# RGBM-04.net
KiCad netlist of a schematic drawn in Altium Designer
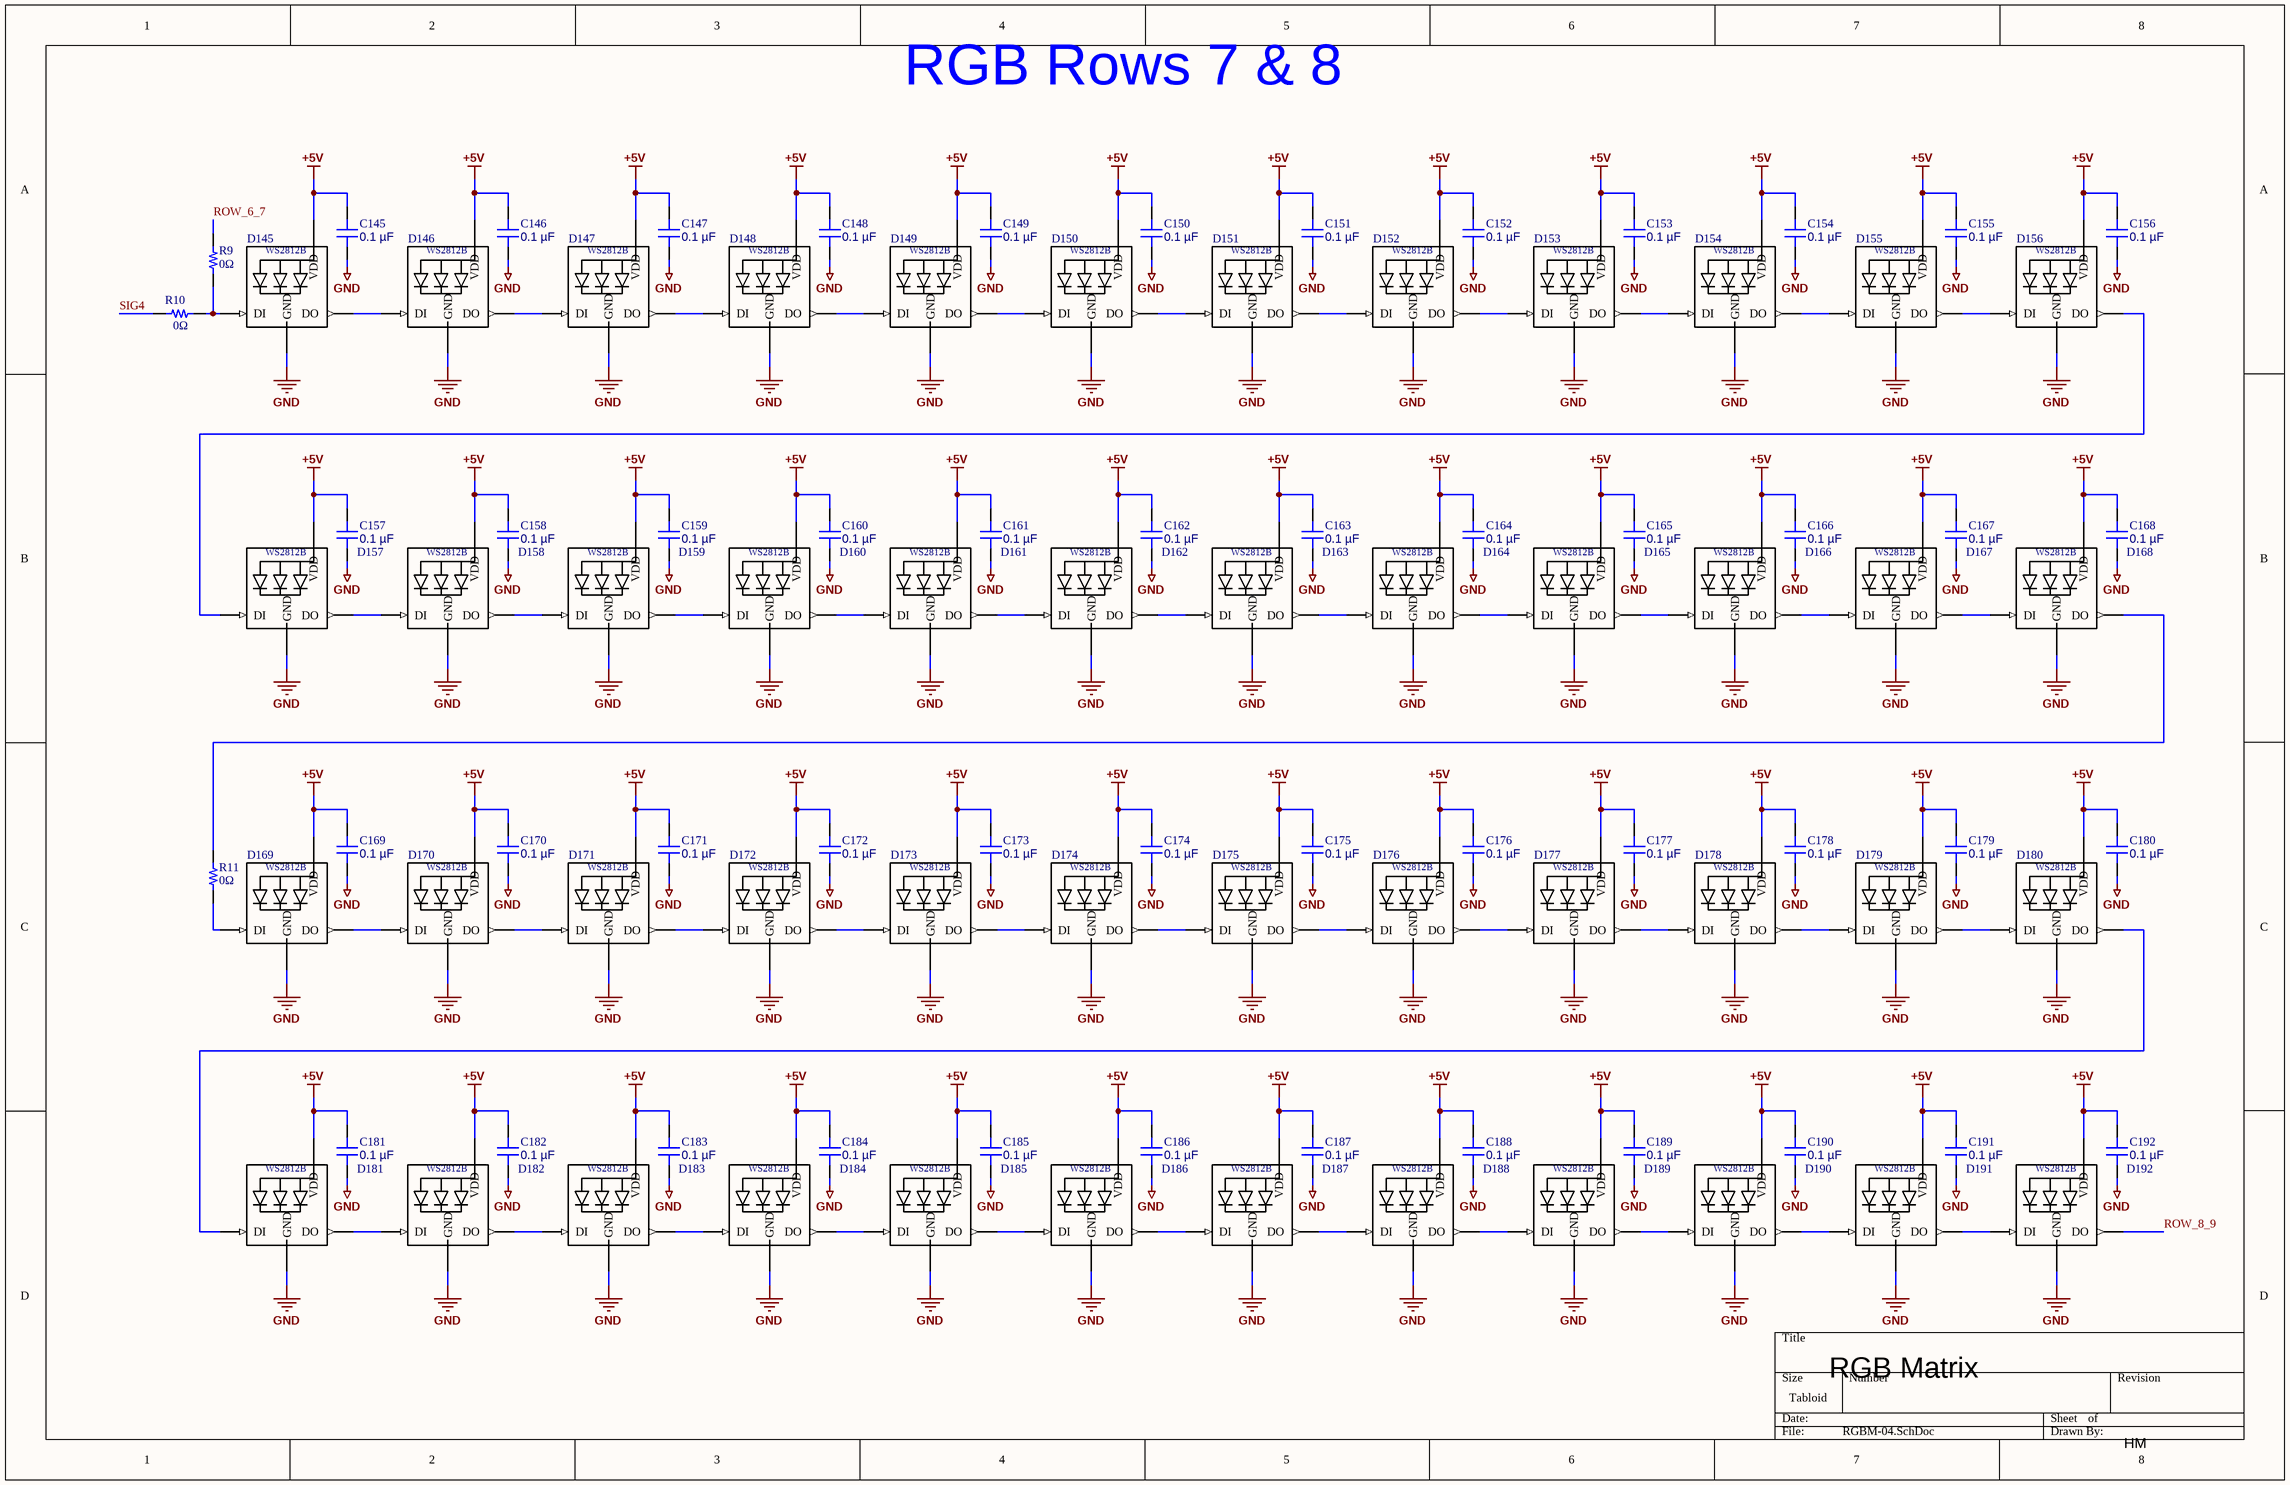
[diagram p0: RGBM-04.SchDoc]

(export (version "E")
  (design (tool "Eeschema 10.0.6"))
  (components
    (comp (ref "C145")
      (value "0.1 µF")
      (footprint "CAP 0603_1608")
      (description "CAP CER 0.1UF 50V X7R 0603")
      (fields
        (field (name "PART NUMBER") "C0603C104K5RAC7411")
        (field (name "CAPACITANCE") "0.1 µF")
        (field (name "MANUFACTURER") "KEMET")
      )
      (libsource (lib "Celestial Altium Library - altium_library") (part "Capacitor"))
    )
    (comp (ref "C146")
      (value "0.1 µF")
      (footprint "CAP 0603_1608")
      (description "CAP CER 0.1UF 50V X7R 0603")
      (fields
        (field (name "PART NUMBER") "C0603C104K5RAC7411")
        (field (name "CAPACITANCE") "0.1 µF")
        (field (name "MANUFACTURER") "KEMET")
      )
      (libsource (lib "Celestial Altium Library - altium_library") (part "Capacitor"))
    )
    (comp (ref "C147")
      (value "0.1 µF")
      (footprint "CAP 0603_1608")
      (description "CAP CER 0.1UF 50V X7R 0603")
      (fields
        (field (name "PART NUMBER") "C0603C104K5RAC7411")
        (field (name "CAPACITANCE") "0.1 µF")
        (field (name "MANUFACTURER") "KEMET")
      )
      (libsource (lib "Celestial Altium Library - altium_library") (part "Capacitor"))
    )
    (comp (ref "C148")
      (value "0.1 µF")
      (footprint "CAP 0603_1608")
      (description "CAP CER 0.1UF 50V X7R 0603")
      (fields
        (field (name "PART NUMBER") "C0603C104K5RAC7411")
        (field (name "CAPACITANCE") "0.1 µF")
        (field (name "MANUFACTURER") "KEMET")
      )
      (libsource (lib "Celestial Altium Library - altium_library") (part "Capacitor"))
    )
    (comp (ref "C149")
      (value "0.1 µF")
      (footprint "CAP 0603_1608")
      (description "CAP CER 0.1UF 50V X7R 0603")
      (fields
        (field (name "PART NUMBER") "C0603C104K5RAC7411")
        (field (name "CAPACITANCE") "0.1 µF")
        (field (name "MANUFACTURER") "KEMET")
      )
      (libsource (lib "Celestial Altium Library - altium_library") (part "Capacitor"))
    )
    (comp (ref "C150")
      (value "0.1 µF")
      (footprint "CAP 0603_1608")
      (description "CAP CER 0.1UF 50V X7R 0603")
      (fields
        (field (name "PART NUMBER") "C0603C104K5RAC7411")
        (field (name "CAPACITANCE") "0.1 µF")
        (field (name "MANUFACTURER") "KEMET")
      )
      (libsource (lib "Celestial Altium Library - altium_library") (part "Capacitor"))
    )
    (comp (ref "C151")
      (value "0.1 µF")
      (footprint "CAP 0603_1608")
      (description "CAP CER 0.1UF 50V X7R 0603")
      (fields
        (field (name "PART NUMBER") "C0603C104K5RAC7411")
        (field (name "CAPACITANCE") "0.1 µF")
        (field (name "MANUFACTURER") "KEMET")
      )
      (libsource (lib "Celestial Altium Library - altium_library") (part "Capacitor"))
    )
    (comp (ref "C152")
      (value "0.1 µF")
      (footprint "CAP 0603_1608")
      (description "CAP CER 0.1UF 50V X7R 0603")
      (fields
        (field (name "PART NUMBER") "C0603C104K5RAC7411")
        (field (name "CAPACITANCE") "0.1 µF")
        (field (name "MANUFACTURER") "KEMET")
      )
      (libsource (lib "Celestial Altium Library - altium_library") (part "Capacitor"))
    )
    (comp (ref "C153")
      (value "0.1 µF")
      (footprint "CAP 0603_1608")
      (description "CAP CER 0.1UF 50V X7R 0603")
      (fields
        (field (name "PART NUMBER") "C0603C104K5RAC7411")
        (field (name "CAPACITANCE") "0.1 µF")
        (field (name "MANUFACTURER") "KEMET")
      )
      (libsource (lib "Celestial Altium Library - altium_library") (part "Capacitor"))
    )
    (comp (ref "C154")
      (value "0.1 µF")
      (footprint "CAP 0603_1608")
      (description "CAP CER 0.1UF 50V X7R 0603")
      (fields
        (field (name "PART NUMBER") "C0603C104K5RAC7411")
        (field (name "CAPACITANCE") "0.1 µF")
        (field (name "MANUFACTURER") "KEMET")
      )
      (libsource (lib "Celestial Altium Library - altium_library") (part "Capacitor"))
    )
    (comp (ref "C155")
      (value "0.1 µF")
      (footprint "CAP 0603_1608")
      (description "CAP CER 0.1UF 50V X7R 0603")
      (fields
        (field (name "PART NUMBER") "C0603C104K5RAC7411")
        (field (name "CAPACITANCE") "0.1 µF")
        (field (name "MANUFACTURER") "KEMET")
      )
      (libsource (lib "Celestial Altium Library - altium_library") (part "Capacitor"))
    )
    (comp (ref "C156")
      (value "0.1 µF")
      (footprint "CAP 0603_1608")
      (description "CAP CER 0.1UF 50V X7R 0603")
      (fields
        (field (name "PART NUMBER") "C0603C104K5RAC7411")
        (field (name "CAPACITANCE") "0.1 µF")
        (field (name "MANUFACTURER") "KEMET")
      )
      (libsource (lib "Celestial Altium Library - altium_library") (part "Capacitor"))
    )
    (comp (ref "C157")
      (value "0.1 µF")
      (footprint "CAP 0603_1608")
      (description "CAP CER 0.1UF 50V X7R 0603")
      (fields
        (field (name "PART NUMBER") "C0603C104K5RAC7411")
        (field (name "CAPACITANCE") "0.1 µF")
        (field (name "MANUFACTURER") "KEMET")
      )
      (libsource (lib "Celestial Altium Library - altium_library") (part "Capacitor"))
    )
    (comp (ref "C158")
      (value "0.1 µF")
      (footprint "CAP 0603_1608")
      (description "CAP CER 0.1UF 50V X7R 0603")
      (fields
        (field (name "PART NUMBER") "C0603C104K5RAC7411")
        (field (name "CAPACITANCE") "0.1 µF")
        (field (name "MANUFACTURER") "KEMET")
      )
      (libsource (lib "Celestial Altium Library - altium_library") (part "Capacitor"))
    )
    (comp (ref "C159")
      (value "0.1 µF")
      (footprint "CAP 0603_1608")
      (description "CAP CER 0.1UF 50V X7R 0603")
      (fields
        (field (name "PART NUMBER") "C0603C104K5RAC7411")
        (field (name "CAPACITANCE") "0.1 µF")
        (field (name "MANUFACTURER") "KEMET")
      )
      (libsource (lib "Celestial Altium Library - altium_library") (part "Capacitor"))
    )
    (comp (ref "C160")
      (value "0.1 µF")
      (footprint "CAP 0603_1608")
      (description "CAP CER 0.1UF 50V X7R 0603")
      (fields
        (field (name "PART NUMBER") "C0603C104K5RAC7411")
        (field (name "CAPACITANCE") "0.1 µF")
        (field (name "MANUFACTURER") "KEMET")
      )
      (libsource (lib "Celestial Altium Library - altium_library") (part "Capacitor"))
    )
    (comp (ref "C161")
      (value "0.1 µF")
      (footprint "CAP 0603_1608")
      (description "CAP CER 0.1UF 50V X7R 0603")
      (fields
        (field (name "PART NUMBER") "C0603C104K5RAC7411")
        (field (name "CAPACITANCE") "0.1 µF")
        (field (name "MANUFACTURER") "KEMET")
      )
      (libsource (lib "Celestial Altium Library - altium_library") (part "Capacitor"))
    )
    (comp (ref "C162")
      (value "0.1 µF")
      (footprint "CAP 0603_1608")
      (description "CAP CER 0.1UF 50V X7R 0603")
      (fields
        (field (name "PART NUMBER") "C0603C104K5RAC7411")
        (field (name "CAPACITANCE") "0.1 µF")
        (field (name "MANUFACTURER") "KEMET")
      )
      (libsource (lib "Celestial Altium Library - altium_library") (part "Capacitor"))
    )
    (comp (ref "C163")
      (value "0.1 µF")
      (footprint "CAP 0603_1608")
      (description "CAP CER 0.1UF 50V X7R 0603")
      (fields
        (field (name "PART NUMBER") "C0603C104K5RAC7411")
        (field (name "CAPACITANCE") "0.1 µF")
        (field (name "MANUFACTURER") "KEMET")
      )
      (libsource (lib "Celestial Altium Library - altium_library") (part "Capacitor"))
    )
    (comp (ref "C164")
      (value "0.1 µF")
      (footprint "CAP 0603_1608")
      (description "CAP CER 0.1UF 50V X7R 0603")
      (fields
        (field (name "PART NUMBER") "C0603C104K5RAC7411")
        (field (name "CAPACITANCE") "0.1 µF")
        (field (name "MANUFACTURER") "KEMET")
      )
      (libsource (lib "Celestial Altium Library - altium_library") (part "Capacitor"))
    )
    (comp (ref "C165")
      (value "0.1 µF")
      (footprint "CAP 0603_1608")
      (description "CAP CER 0.1UF 50V X7R 0603")
      (fields
        (field (name "PART NUMBER") "C0603C104K5RAC7411")
        (field (name "CAPACITANCE") "0.1 µF")
        (field (name "MANUFACTURER") "KEMET")
      )
      (libsource (lib "Celestial Altium Library - altium_library") (part "Capacitor"))
    )
    (comp (ref "C166")
      (value "0.1 µF")
      (footprint "CAP 0603_1608")
      (description "CAP CER 0.1UF 50V X7R 0603")
      (fields
        (field (name "PART NUMBER") "C0603C104K5RAC7411")
        (field (name "CAPACITANCE") "0.1 µF")
        (field (name "MANUFACTURER") "KEMET")
      )
      (libsource (lib "Celestial Altium Library - altium_library") (part "Capacitor"))
    )
    (comp (ref "C167")
      (value "0.1 µF")
      (footprint "CAP 0603_1608")
      (description "CAP CER 0.1UF 50V X7R 0603")
      (fields
        (field (name "PART NUMBER") "C0603C104K5RAC7411")
        (field (name "CAPACITANCE") "0.1 µF")
        (field (name "MANUFACTURER") "KEMET")
      )
      (libsource (lib "Celestial Altium Library - altium_library") (part "Capacitor"))
    )
    (comp (ref "C168")
      (value "0.1 µF")
      (footprint "CAP 0603_1608")
      (description "CAP CER 0.1UF 50V X7R 0603")
      (fields
        (field (name "PART NUMBER") "C0603C104K5RAC7411")
        (field (name "CAPACITANCE") "0.1 µF")
        (field (name "MANUFACTURER") "KEMET")
      )
      (libsource (lib "Celestial Altium Library - altium_library") (part "Capacitor"))
    )
    (comp (ref "C169")
      (value "0.1 µF")
      (footprint "CAP 0603_1608")
      (description "CAP CER 0.1UF 50V X7R 0603")
      (fields
        (field (name "PART NUMBER") "C0603C104K5RAC7411")
        (field (name "CAPACITANCE") "0.1 µF")
        (field (name "MANUFACTURER") "KEMET")
      )
      (libsource (lib "Celestial Altium Library - altium_library") (part "Capacitor"))
    )
    (comp (ref "C170")
      (value "0.1 µF")
      (footprint "CAP 0603_1608")
      (description "CAP CER 0.1UF 50V X7R 0603")
      (fields
        (field (name "PART NUMBER") "C0603C104K5RAC7411")
        (field (name "CAPACITANCE") "0.1 µF")
        (field (name "MANUFACTURER") "KEMET")
      )
      (libsource (lib "Celestial Altium Library - altium_library") (part "Capacitor"))
    )
    (comp (ref "C171")
      (value "0.1 µF")
      (footprint "CAP 0603_1608")
      (description "CAP CER 0.1UF 50V X7R 0603")
      (fields
        (field (name "PART NUMBER") "C0603C104K5RAC7411")
        (field (name "CAPACITANCE") "0.1 µF")
        (field (name "MANUFACTURER") "KEMET")
      )
      (libsource (lib "Celestial Altium Library - altium_library") (part "Capacitor"))
    )
    (comp (ref "C172")
      (value "0.1 µF")
      (footprint "CAP 0603_1608")
      (description "CAP CER 0.1UF 50V X7R 0603")
      (fields
        (field (name "PART NUMBER") "C0603C104K5RAC7411")
        (field (name "CAPACITANCE") "0.1 µF")
        (field (name "MANUFACTURER") "KEMET")
      )
      (libsource (lib "Celestial Altium Library - altium_library") (part "Capacitor"))
    )
    (comp (ref "C173")
      (value "0.1 µF")
      (footprint "CAP 0603_1608")
      (description "CAP CER 0.1UF 50V X7R 0603")
      (fields
        (field (name "PART NUMBER") "C0603C104K5RAC7411")
        (field (name "CAPACITANCE") "0.1 µF")
        (field (name "MANUFACTURER") "KEMET")
      )
      (libsource (lib "Celestial Altium Library - altium_library") (part "Capacitor"))
    )
    (comp (ref "C174")
      (value "0.1 µF")
      (footprint "CAP 0603_1608")
      (description "CAP CER 0.1UF 50V X7R 0603")
      (fields
        (field (name "PART NUMBER") "C0603C104K5RAC7411")
        (field (name "CAPACITANCE") "0.1 µF")
        (field (name "MANUFACTURER") "KEMET")
      )
      (libsource (lib "Celestial Altium Library - altium_library") (part "Capacitor"))
    )
    (comp (ref "C175")
      (value "0.1 µF")
      (footprint "CAP 0603_1608")
      (description "CAP CER 0.1UF 50V X7R 0603")
      (fields
        (field (name "PART NUMBER") "C0603C104K5RAC7411")
        (field (name "CAPACITANCE") "0.1 µF")
        (field (name "MANUFACTURER") "KEMET")
      )
      (libsource (lib "Celestial Altium Library - altium_library") (part "Capacitor"))
    )
    (comp (ref "C176")
      (value "0.1 µF")
      (footprint "CAP 0603_1608")
      (description "CAP CER 0.1UF 50V X7R 0603")
      (fields
        (field (name "PART NUMBER") "C0603C104K5RAC7411")
        (field (name "CAPACITANCE") "0.1 µF")
        (field (name "MANUFACTURER") "KEMET")
      )
      (libsource (lib "Celestial Altium Library - altium_library") (part "Capacitor"))
    )
    (comp (ref "C177")
      (value "0.1 µF")
      (footprint "CAP 0603_1608")
      (description "CAP CER 0.1UF 50V X7R 0603")
      (fields
        (field (name "PART NUMBER") "C0603C104K5RAC7411")
        (field (name "CAPACITANCE") "0.1 µF")
        (field (name "MANUFACTURER") "KEMET")
      )
      (libsource (lib "Celestial Altium Library - altium_library") (part "Capacitor"))
    )
    (comp (ref "C178")
      (value "0.1 µF")
      (footprint "CAP 0603_1608")
      (description "CAP CER 0.1UF 50V X7R 0603")
      (fields
        (field (name "PART NUMBER") "C0603C104K5RAC7411")
        (field (name "CAPACITANCE") "0.1 µF")
        (field (name "MANUFACTURER") "KEMET")
      )
      (libsource (lib "Celestial Altium Library - altium_library") (part "Capacitor"))
    )
    (comp (ref "C179")
      (value "0.1 µF")
      (footprint "CAP 0603_1608")
      (description "CAP CER 0.1UF 50V X7R 0603")
      (fields
        (field (name "PART NUMBER") "C0603C104K5RAC7411")
        (field (name "CAPACITANCE") "0.1 µF")
        (field (name "MANUFACTURER") "KEMET")
      )
      (libsource (lib "Celestial Altium Library - altium_library") (part "Capacitor"))
    )
    (comp (ref "C180")
      (value "0.1 µF")
      (footprint "CAP 0603_1608")
      (description "CAP CER 0.1UF 50V X7R 0603")
      (fields
        (field (name "PART NUMBER") "C0603C104K5RAC7411")
        (field (name "CAPACITANCE") "0.1 µF")
        (field (name "MANUFACTURER") "KEMET")
      )
      (libsource (lib "Celestial Altium Library - altium_library") (part "Capacitor"))
    )
    (comp (ref "C181")
      (value "0.1 µF")
      (footprint "CAP 0603_1608")
      (description "CAP CER 0.1UF 50V X7R 0603")
      (fields
        (field (name "PART NUMBER") "C0603C104K5RAC7411")
        (field (name "CAPACITANCE") "0.1 µF")
        (field (name "MANUFACTURER") "KEMET")
      )
      (libsource (lib "Celestial Altium Library - altium_library") (part "Capacitor"))
    )
    (comp (ref "C182")
      (value "0.1 µF")
      (footprint "CAP 0603_1608")
      (description "CAP CER 0.1UF 50V X7R 0603")
      (fields
        (field (name "PART NUMBER") "C0603C104K5RAC7411")
        (field (name "CAPACITANCE") "0.1 µF")
        (field (name "MANUFACTURER") "KEMET")
      )
      (libsource (lib "Celestial Altium Library - altium_library") (part "Capacitor"))
    )
    (comp (ref "C183")
      (value "0.1 µF")
      (footprint "CAP 0603_1608")
      (description "CAP CER 0.1UF 50V X7R 0603")
      (fields
        (field (name "PART NUMBER") "C0603C104K5RAC7411")
        (field (name "CAPACITANCE") "0.1 µF")
        (field (name "MANUFACTURER") "KEMET")
      )
      (libsource (lib "Celestial Altium Library - altium_library") (part "Capacitor"))
    )
    (comp (ref "C184")
      (value "0.1 µF")
      (footprint "CAP 0603_1608")
      (description "CAP CER 0.1UF 50V X7R 0603")
      (fields
        (field (name "PART NUMBER") "C0603C104K5RAC7411")
        (field (name "CAPACITANCE") "0.1 µF")
        (field (name "MANUFACTURER") "KEMET")
      )
      (libsource (lib "Celestial Altium Library - altium_library") (part "Capacitor"))
    )
    (comp (ref "C185")
      (value "0.1 µF")
      (footprint "CAP 0603_1608")
      (description "CAP CER 0.1UF 50V X7R 0603")
      (fields
        (field (name "PART NUMBER") "C0603C104K5RAC7411")
        (field (name "CAPACITANCE") "0.1 µF")
        (field (name "MANUFACTURER") "KEMET")
      )
      (libsource (lib "Celestial Altium Library - altium_library") (part "Capacitor"))
    )
    (comp (ref "C186")
      (value "0.1 µF")
      (footprint "CAP 0603_1608")
      (description "CAP CER 0.1UF 50V X7R 0603")
      (fields
        (field (name "PART NUMBER") "C0603C104K5RAC7411")
        (field (name "CAPACITANCE") "0.1 µF")
        (field (name "MANUFACTURER") "KEMET")
      )
      (libsource (lib "Celestial Altium Library - altium_library") (part "Capacitor"))
    )
    (comp (ref "C187")
      (value "0.1 µF")
      (footprint "CAP 0603_1608")
      (description "CAP CER 0.1UF 50V X7R 0603")
      (fields
        (field (name "PART NUMBER") "C0603C104K5RAC7411")
        (field (name "CAPACITANCE") "0.1 µF")
        (field (name "MANUFACTURER") "KEMET")
      )
      (libsource (lib "Celestial Altium Library - altium_library") (part "Capacitor"))
    )
    (comp (ref "C188")
      (value "0.1 µF")
      (footprint "CAP 0603_1608")
      (description "CAP CER 0.1UF 50V X7R 0603")
      (fields
        (field (name "PART NUMBER") "C0603C104K5RAC7411")
        (field (name "CAPACITANCE") "0.1 µF")
        (field (name "MANUFACTURER") "KEMET")
      )
      (libsource (lib "Celestial Altium Library - altium_library") (part "Capacitor"))
    )
    (comp (ref "C189")
      (value "0.1 µF")
      (footprint "CAP 0603_1608")
      (description "CAP CER 0.1UF 50V X7R 0603")
      (fields
        (field (name "PART NUMBER") "C0603C104K5RAC7411")
        (field (name "CAPACITANCE") "0.1 µF")
        (field (name "MANUFACTURER") "KEMET")
      )
      (libsource (lib "Celestial Altium Library - altium_library") (part "Capacitor"))
    )
    (comp (ref "C190")
      (value "0.1 µF")
      (footprint "CAP 0603_1608")
      (description "CAP CER 0.1UF 50V X7R 0603")
      (fields
        (field (name "PART NUMBER") "C0603C104K5RAC7411")
        (field (name "CAPACITANCE") "0.1 µF")
        (field (name "MANUFACTURER") "KEMET")
      )
      (libsource (lib "Celestial Altium Library - altium_library") (part "Capacitor"))
    )
    (comp (ref "C191")
      (value "0.1 µF")
      (footprint "CAP 0603_1608")
      (description "CAP CER 0.1UF 50V X7R 0603")
      (fields
        (field (name "PART NUMBER") "C0603C104K5RAC7411")
        (field (name "CAPACITANCE") "0.1 µF")
        (field (name "MANUFACTURER") "KEMET")
      )
      (libsource (lib "Celestial Altium Library - altium_library") (part "Capacitor"))
    )
    (comp (ref "C192")
      (value "0.1 µF")
      (footprint "CAP 0603_1608")
      (description "CAP CER 0.1UF 50V X7R 0603")
      (fields
        (field (name "PART NUMBER") "C0603C104K5RAC7411")
        (field (name "CAPACITANCE") "0.1 µF")
        (field (name "MANUFACTURER") "KEMET")
      )
      (libsource (lib "Celestial Altium Library - altium_library") (part "Capacitor"))
    )
    (comp (ref "D145")
      (value "WS2812B")
      (footprint "*WS2812B_WS2812B(Primary)")
      (description "Intelligent control LED integrated light source")
      (fields (field (name "MF") "Worldsemi"))
      (libsource (lib "WS2812B") (part "WS2812B"))
    )
    (comp (ref "D146")
      (value "WS2812B")
      (footprint "*WS2812B_WS2812B(Primary)")
      (description "Intelligent control LED integrated light source")
      (fields (field (name "MF") "Worldsemi"))
      (libsource (lib "WS2812B") (part "WS2812B"))
    )
    (comp (ref "D147")
      (value "WS2812B")
      (footprint "*WS2812B_WS2812B(Primary)")
      (description "Intelligent control LED integrated light source")
      (fields (field (name "MF") "Worldsemi"))
      (libsource (lib "WS2812B") (part "WS2812B"))
    )
    (comp (ref "D148")
      (value "WS2812B")
      (footprint "*WS2812B_WS2812B(Primary)")
      (description "Intelligent control LED integrated light source")
      (fields (field (name "MF") "Worldsemi"))
      (libsource (lib "WS2812B") (part "WS2812B"))
    )
    (comp (ref "D149")
      (value "WS2812B")
      (footprint "*WS2812B_WS2812B(Primary)")
      (description "Intelligent control LED integrated light source")
      (fields (field (name "MF") "Worldsemi"))
      (libsource (lib "WS2812B") (part "WS2812B"))
    )
    (comp (ref "D150")
      (value "WS2812B")
      (footprint "*WS2812B_WS2812B(Primary)")
      (description "Intelligent control LED integrated light source")
      (fields (field (name "MF") "Worldsemi"))
      (libsource (lib "WS2812B") (part "WS2812B"))
    )
    (comp (ref "D151")
      (value "WS2812B")
      (footprint "*WS2812B_WS2812B(Primary)")
      (description "Intelligent control LED integrated light source")
      (fields (field (name "MF") "Worldsemi"))
      (libsource (lib "WS2812B") (part "WS2812B"))
    )
    (comp (ref "D152")
      (value "WS2812B")
      (footprint "*WS2812B_WS2812B(Primary)")
      (description "Intelligent control LED integrated light source")
      (fields (field (name "MF") "Worldsemi"))
      (libsource (lib "WS2812B") (part "WS2812B"))
    )
    (comp (ref "D153")
      (value "WS2812B")
      (footprint "*WS2812B_WS2812B(Primary)")
      (description "Intelligent control LED integrated light source")
      (fields (field (name "MF") "Worldsemi"))
      (libsource (lib "WS2812B") (part "WS2812B"))
    )
    (comp (ref "D154")
      (value "WS2812B")
      (footprint "*WS2812B_WS2812B(Primary)")
      (description "Intelligent control LED integrated light source")
      (fields (field (name "MF") "Worldsemi"))
      (libsource (lib "WS2812B") (part "WS2812B"))
    )
    (comp (ref "D155")
      (value "WS2812B")
      (footprint "*WS2812B_WS2812B(Primary)")
      (description "Intelligent control LED integrated light source")
      (fields (field (name "MF") "Worldsemi"))
      (libsource (lib "WS2812B") (part "WS2812B"))
    )
    (comp (ref "D156")
      (value "WS2812B")
      (footprint "*WS2812B_WS2812B(Primary)")
      (description "Intelligent control LED integrated light source")
      (fields (field (name "MF") "Worldsemi"))
      (libsource (lib "WS2812B") (part "WS2812B"))
    )
    (comp (ref "D157")
      (value "WS2812B")
      (footprint "*WS2812B_WS2812B(Primary)")
      (description "Intelligent control LED integrated light source")
      (fields (field (name "MF") "Worldsemi"))
      (libsource (lib "WS2812B") (part "WS2812B"))
    )
    (comp (ref "D158")
      (value "WS2812B")
      (footprint "*WS2812B_WS2812B(Primary)")
      (description "Intelligent control LED integrated light source")
      (fields (field (name "MF") "Worldsemi"))
      (libsource (lib "WS2812B") (part "WS2812B"))
    )
    (comp (ref "D159")
      (value "WS2812B")
      (footprint "*WS2812B_WS2812B(Primary)")
      (description "Intelligent control LED integrated light source")
      (fields (field (name "MF") "Worldsemi"))
      (libsource (lib "WS2812B") (part "WS2812B"))
    )
    (comp (ref "D160")
      (value "WS2812B")
      (footprint "*WS2812B_WS2812B(Primary)")
      (description "Intelligent control LED integrated light source")
      (fields (field (name "MF") "Worldsemi"))
      (libsource (lib "WS2812B") (part "WS2812B"))
    )
    (comp (ref "D161")
      (value "WS2812B")
      (footprint "*WS2812B_WS2812B(Primary)")
      (description "Intelligent control LED integrated light source")
      (fields (field (name "MF") "Worldsemi"))
      (libsource (lib "WS2812B") (part "WS2812B"))
    )
    (comp (ref "D162")
      (value "WS2812B")
      (footprint "*WS2812B_WS2812B(Primary)")
      (description "Intelligent control LED integrated light source")
      (fields (field (name "MF") "Worldsemi"))
      (libsource (lib "WS2812B") (part "WS2812B"))
    )
    (comp (ref "D163")
      (value "WS2812B")
      (footprint "*WS2812B_WS2812B(Primary)")
      (description "Intelligent control LED integrated light source")
      (fields (field (name "MF") "Worldsemi"))
      (libsource (lib "WS2812B") (part "WS2812B"))
    )
    (comp (ref "D164")
      (value "WS2812B")
      (footprint "*WS2812B_WS2812B(Primary)")
      (description "Intelligent control LED integrated light source")
      (fields (field (name "MF") "Worldsemi"))
      (libsource (lib "WS2812B") (part "WS2812B"))
    )
    (comp (ref "D165")
      (value "WS2812B")
      (footprint "*WS2812B_WS2812B(Primary)")
      (description "Intelligent control LED integrated light source")
      (fields (field (name "MF") "Worldsemi"))
      (libsource (lib "WS2812B") (part "WS2812B"))
    )
    (comp (ref "D166")
      (value "WS2812B")
      (footprint "*WS2812B_WS2812B(Primary)")
      (description "Intelligent control LED integrated light source")
      (fields (field (name "MF") "Worldsemi"))
      (libsource (lib "WS2812B") (part "WS2812B"))
    )
    (comp (ref "D167")
      (value "WS2812B")
      (footprint "*WS2812B_WS2812B(Primary)")
      (description "Intelligent control LED integrated light source")
      (fields (field (name "MF") "Worldsemi"))
      (libsource (lib "WS2812B") (part "WS2812B"))
    )
    (comp (ref "D168")
      (value "WS2812B")
      (footprint "*WS2812B_WS2812B(Primary)")
      (description "Intelligent control LED integrated light source")
      (fields (field (name "MF") "Worldsemi"))
      (libsource (lib "WS2812B") (part "WS2812B"))
    )
    (comp (ref "D169")
      (value "WS2812B")
      (footprint "*WS2812B_WS2812B(Primary)")
      (description "Intelligent control LED integrated light source")
      (fields (field (name "MF") "Worldsemi"))
      (libsource (lib "WS2812B") (part "WS2812B"))
    )
    (comp (ref "D170")
      (value "WS2812B")
      (footprint "*WS2812B_WS2812B(Primary)")
      (description "Intelligent control LED integrated light source")
      (fields (field (name "MF") "Worldsemi"))
      (libsource (lib "WS2812B") (part "WS2812B"))
    )
    (comp (ref "D171")
      (value "WS2812B")
      (footprint "*WS2812B_WS2812B(Primary)")
      (description "Intelligent control LED integrated light source")
      (fields (field (name "MF") "Worldsemi"))
      (libsource (lib "WS2812B") (part "WS2812B"))
    )
    (comp (ref "D172")
      (value "WS2812B")
      (footprint "*WS2812B_WS2812B(Primary)")
      (description "Intelligent control LED integrated light source")
      (fields (field (name "MF") "Worldsemi"))
      (libsource (lib "WS2812B") (part "WS2812B"))
    )
    (comp (ref "D173")
      (value "WS2812B")
      (footprint "*WS2812B_WS2812B(Primary)")
      (description "Intelligent control LED integrated light source")
      (fields (field (name "MF") "Worldsemi"))
      (libsource (lib "WS2812B") (part "WS2812B"))
    )
    (comp (ref "D174")
      (value "WS2812B")
      (footprint "*WS2812B_WS2812B(Primary)")
      (description "Intelligent control LED integrated light source")
      (fields (field (name "MF") "Worldsemi"))
      (libsource (lib "WS2812B") (part "WS2812B"))
    )
    (comp (ref "D175")
      (value "WS2812B")
      (footprint "*WS2812B_WS2812B(Primary)")
      (description "Intelligent control LED integrated light source")
      (fields (field (name "MF") "Worldsemi"))
      (libsource (lib "WS2812B") (part "WS2812B"))
    )
    (comp (ref "D176")
      (value "WS2812B")
      (footprint "*WS2812B_WS2812B(Primary)")
      (description "Intelligent control LED integrated light source")
      (fields (field (name "MF") "Worldsemi"))
      (libsource (lib "WS2812B") (part "WS2812B"))
    )
    (comp (ref "D177")
      (value "WS2812B")
      (footprint "*WS2812B_WS2812B(Primary)")
      (description "Intelligent control LED integrated light source")
      (fields (field (name "MF") "Worldsemi"))
      (libsource (lib "WS2812B") (part "WS2812B"))
    )
    (comp (ref "D178")
      (value "WS2812B")
      (footprint "*WS2812B_WS2812B(Primary)")
      (description "Intelligent control LED integrated light source")
      (fields (field (name "MF") "Worldsemi"))
      (libsource (lib "WS2812B") (part "WS2812B"))
    )
    (comp (ref "D179")
      (value "WS2812B")
      (footprint "*WS2812B_WS2812B(Primary)")
      (description "Intelligent control LED integrated light source")
      (fields (field (name "MF") "Worldsemi"))
      (libsource (lib "WS2812B") (part "WS2812B"))
    )
    (comp (ref "D180")
      (value "WS2812B")
      (footprint "*WS2812B_WS2812B(Primary)")
      (description "Intelligent control LED integrated light source")
      (fields (field (name "MF") "Worldsemi"))
      (libsource (lib "WS2812B") (part "WS2812B"))
    )
    (comp (ref "D181")
      (value "WS2812B")
      (footprint "*WS2812B_WS2812B(Primary)")
      (description "Intelligent control LED integrated light source")
      (fields (field (name "MF") "Worldsemi"))
      (libsource (lib "WS2812B") (part "WS2812B"))
    )
    (comp (ref "D182")
      (value "WS2812B")
      (footprint "*WS2812B_WS2812B(Primary)")
      (description "Intelligent control LED integrated light source")
      (fields (field (name "MF") "Worldsemi"))
      (libsource (lib "WS2812B") (part "WS2812B"))
    )
    (comp (ref "D183")
      (value "WS2812B")
      (footprint "*WS2812B_WS2812B(Primary)")
      (description "Intelligent control LED integrated light source")
      (fields (field (name "MF") "Worldsemi"))
      (libsource (lib "WS2812B") (part "WS2812B"))
    )
    (comp (ref "D184")
      (value "WS2812B")
      (footprint "*WS2812B_WS2812B(Primary)")
      (description "Intelligent control LED integrated light source")
      (fields (field (name "MF") "Worldsemi"))
      (libsource (lib "WS2812B") (part "WS2812B"))
    )
    (comp (ref "D185")
      (value "WS2812B")
      (footprint "*WS2812B_WS2812B(Primary)")
      (description "Intelligent control LED integrated light source")
      (fields (field (name "MF") "Worldsemi"))
      (libsource (lib "WS2812B") (part "WS2812B"))
    )
    (comp (ref "D186")
      (value "WS2812B")
      (footprint "*WS2812B_WS2812B(Primary)")
      (description "Intelligent control LED integrated light source")
      (fields (field (name "MF") "Worldsemi"))
      (libsource (lib "WS2812B") (part "WS2812B"))
    )
    (comp (ref "D187")
      (value "WS2812B")
      (footprint "*WS2812B_WS2812B(Primary)")
      (description "Intelligent control LED integrated light source")
      (fields (field (name "MF") "Worldsemi"))
      (libsource (lib "WS2812B") (part "WS2812B"))
    )
    (comp (ref "D188")
      (value "WS2812B")
      (footprint "*WS2812B_WS2812B(Primary)")
      (description "Intelligent control LED integrated light source")
      (fields (field (name "MF") "Worldsemi"))
      (libsource (lib "WS2812B") (part "WS2812B"))
    )
    (comp (ref "D189")
      (value "WS2812B")
      (footprint "*WS2812B_WS2812B(Primary)")
      (description "Intelligent control LED integrated light source")
      (fields (field (name "MF") "Worldsemi"))
      (libsource (lib "WS2812B") (part "WS2812B"))
    )
    (comp (ref "D190")
      (value "WS2812B")
      (footprint "*WS2812B_WS2812B(Primary)")
      (description "Intelligent control LED integrated light source")
      (fields (field (name "MF") "Worldsemi"))
      (libsource (lib "WS2812B") (part "WS2812B"))
    )
    (comp (ref "D191")
      (value "WS2812B")
      (footprint "*WS2812B_WS2812B(Primary)")
      (description "Intelligent control LED integrated light source")
      (fields (field (name "MF") "Worldsemi"))
      (libsource (lib "WS2812B") (part "WS2812B"))
    )
    (comp (ref "D192")
      (value "WS2812B")
      (footprint "*WS2812B_WS2812B(Primary)")
      (description "Intelligent control LED integrated light source")
      (fields (field (name "MF") "Worldsemi"))
      (libsource (lib "WS2812B") (part "WS2812B"))
    )
    (comp (ref "R9")
      (value "0Ω")
      (footprint "RES 0603_1608")
      (description "RES SMD 0 OHM JUMPER 0603")
      (fields (field (name "PART NUMBER") "YJP1608-R001") (field (name "MANUFACTURER") "Susumu"))
      (libsource (lib "Celestial Altium Library - altium_library") (part "Resistor"))
    )
    (comp (ref "R10")
      (value "0Ω")
      (footprint "RES 0603_1608")
      (description "RES SMD 0 OHM JUMPER 0603")
      (fields (field (name "PART NUMBER") "YJP1608-R001") (field (name "MANUFACTURER") "Susumu"))
      (libsource (lib "Celestial Altium Library - altium_library") (part "Resistor"))
    )
    (comp (ref "R11")
      (value "0Ω")
      (footprint "RES 0603_1608")
      (description "RES SMD 0 OHM JUMPER 0603")
      (fields (field (name "PART NUMBER") "YJP1608-R001") (field (name "MANUFACTURER") "Susumu"))
      (libsource (lib "Celestial Altium Library - altium_library") (part "Resistor"))
    )
  )
  (nets
    (net (code "1") (name "+5V") (class "Default")
      (node (ref "C145") (pin "2") (pinfunction "2_2") (pintype "passive"))
      (node (ref "C146") (pin "2") (pinfunction "2_2") (pintype "passive"))
      (node (ref "C147") (pin "2") (pinfunction "2_2") (pintype "passive"))
      (node (ref "C148") (pin "2") (pinfunction "2_2") (pintype "passive"))
      (node (ref "C149") (pin "2") (pinfunction "2_2") (pintype "passive"))
      (node (ref "C150") (pin "2") (pinfunction "2_2") (pintype "passive"))
      (node (ref "C151") (pin "2") (pinfunction "2_2") (pintype "passive"))
      (node (ref "C152") (pin "2") (pinfunction "2_2") (pintype "passive"))
      (node (ref "C153") (pin "2") (pinfunction "2_2") (pintype "passive"))
      (node (ref "C154") (pin "2") (pinfunction "2_2") (pintype "passive"))
      (node (ref "C155") (pin "2") (pinfunction "2_2") (pintype "passive"))
      (node (ref "C156") (pin "2") (pinfunction "2_2") (pintype "passive"))
      (node (ref "C157") (pin "2") (pinfunction "2_2") (pintype "passive"))
      (node (ref "C158") (pin "2") (pinfunction "2_2") (pintype "passive"))
      (node (ref "C159") (pin "2") (pinfunction "2_2") (pintype "passive"))
      (node (ref "C160") (pin "2") (pinfunction "2_2") (pintype "passive"))
      (node (ref "C161") (pin "2") (pinfunction "2_2") (pintype "passive"))
      (node (ref "C162") (pin "2") (pinfunction "2_2") (pintype "passive"))
      (node (ref "C163") (pin "2") (pinfunction "2_2") (pintype "passive"))
      (node (ref "C164") (pin "2") (pinfunction "2_2") (pintype "passive"))
      (node (ref "C165") (pin "2") (pinfunction "2_2") (pintype "passive"))
      (node (ref "C166") (pin "2") (pinfunction "2_2") (pintype "passive"))
      (node (ref "C167") (pin "2") (pinfunction "2_2") (pintype "passive"))
      (node (ref "C168") (pin "2") (pinfunction "2_2") (pintype "passive"))
      (node (ref "C169") (pin "2") (pinfunction "2_2") (pintype "passive"))
      (node (ref "C170") (pin "2") (pinfunction "2_2") (pintype "passive"))
      (node (ref "C171") (pin "2") (pinfunction "2_2") (pintype "passive"))
      (node (ref "C172") (pin "2") (pinfunction "2_2") (pintype "passive"))
      (node (ref "C173") (pin "2") (pinfunction "2_2") (pintype "passive"))
      (node (ref "C174") (pin "2") (pinfunction "2_2") (pintype "passive"))
      (node (ref "C175") (pin "2") (pinfunction "2_2") (pintype "passive"))
      (node (ref "C176") (pin "2") (pinfunction "2_2") (pintype "passive"))
      (node (ref "C177") (pin "2") (pinfunction "2_2") (pintype "passive"))
      (node (ref "C178") (pin "2") (pinfunction "2_2") (pintype "passive"))
      (node (ref "C179") (pin "2") (pinfunction "2_2") (pintype "passive"))
      (node (ref "C180") (pin "2") (pinfunction "2_2") (pintype "passive"))
      (node (ref "C181") (pin "2") (pinfunction "2_2") (pintype "passive"))
      (node (ref "C182") (pin "2") (pinfunction "2_2") (pintype "passive"))
      (node (ref "C183") (pin "2") (pinfunction "2_2") (pintype "passive"))
      (node (ref "C184") (pin "2") (pinfunction "2_2") (pintype "passive"))
      (node (ref "C185") (pin "2") (pinfunction "2_2") (pintype "passive"))
      (node (ref "C186") (pin "2") (pinfunction "2_2") (pintype "passive"))
      (node (ref "C187") (pin "2") (pinfunction "2_2") (pintype "passive"))
      (node (ref "C188") (pin "2") (pinfunction "2_2") (pintype "passive"))
      (node (ref "C189") (pin "2") (pinfunction "2_2") (pintype "passive"))
      (node (ref "C190") (pin "2") (pinfunction "2_2") (pintype "passive"))
      (node (ref "C191") (pin "2") (pinfunction "2_2") (pintype "passive"))
      (node (ref "C192") (pin "2") (pinfunction "2_2") (pintype "passive"))
      (node (ref "D145") (pin "1-VDD") (pinfunction "VDD_1-VDD") (pintype "power_in"))
      (node (ref "D146") (pin "1-VDD") (pinfunction "VDD_1-VDD") (pintype "power_in"))
      (node (ref "D147") (pin "1-VDD") (pinfunction "VDD_1-VDD") (pintype "power_in"))
      (node (ref "D148") (pin "1-VDD") (pinfunction "VDD_1-VDD") (pintype "power_in"))
      (node (ref "D149") (pin "1-VDD") (pinfunction "VDD_1-VDD") (pintype "power_in"))
      (node (ref "D150") (pin "1-VDD") (pinfunction "VDD_1-VDD") (pintype "power_in"))
      (node (ref "D151") (pin "1-VDD") (pinfunction "VDD_1-VDD") (pintype "power_in"))
      (node (ref "D152") (pin "1-VDD") (pinfunction "VDD_1-VDD") (pintype "power_in"))
      (node (ref "D153") (pin "1-VDD") (pinfunction "VDD_1-VDD") (pintype "power_in"))
      (node (ref "D154") (pin "1-VDD") (pinfunction "VDD_1-VDD") (pintype "power_in"))
      (node (ref "D155") (pin "1-VDD") (pinfunction "VDD_1-VDD") (pintype "power_in"))
      (node (ref "D156") (pin "1-VDD") (pinfunction "VDD_1-VDD") (pintype "power_in"))
      (node (ref "D157") (pin "1-VDD") (pinfunction "VDD_1-VDD") (pintype "power_in"))
      (node (ref "D158") (pin "1-VDD") (pinfunction "VDD_1-VDD") (pintype "power_in"))
      (node (ref "D159") (pin "1-VDD") (pinfunction "VDD_1-VDD") (pintype "power_in"))
      (node (ref "D160") (pin "1-VDD") (pinfunction "VDD_1-VDD") (pintype "power_in"))
      (node (ref "D161") (pin "1-VDD") (pinfunction "VDD_1-VDD") (pintype "power_in"))
      (node (ref "D162") (pin "1-VDD") (pinfunction "VDD_1-VDD") (pintype "power_in"))
      (node (ref "D163") (pin "1-VDD") (pinfunction "VDD_1-VDD") (pintype "power_in"))
      (node (ref "D164") (pin "1-VDD") (pinfunction "VDD_1-VDD") (pintype "power_in"))
      (node (ref "D165") (pin "1-VDD") (pinfunction "VDD_1-VDD") (pintype "power_in"))
      (node (ref "D166") (pin "1-VDD") (pinfunction "VDD_1-VDD") (pintype "power_in"))
      (node (ref "D167") (pin "1-VDD") (pinfunction "VDD_1-VDD") (pintype "power_in"))
      (node (ref "D168") (pin "1-VDD") (pinfunction "VDD_1-VDD") (pintype "power_in"))
      (node (ref "D169") (pin "1-VDD") (pinfunction "VDD_1-VDD") (pintype "power_in"))
      (node (ref "D170") (pin "1-VDD") (pinfunction "VDD_1-VDD") (pintype "power_in"))
      (node (ref "D171") (pin "1-VDD") (pinfunction "VDD_1-VDD") (pintype "power_in"))
      (node (ref "D172") (pin "1-VDD") (pinfunction "VDD_1-VDD") (pintype "power_in"))
      (node (ref "D173") (pin "1-VDD") (pinfunction "VDD_1-VDD") (pintype "power_in"))
      (node (ref "D174") (pin "1-VDD") (pinfunction "VDD_1-VDD") (pintype "power_in"))
      (node (ref "D175") (pin "1-VDD") (pinfunction "VDD_1-VDD") (pintype "power_in"))
      (node (ref "D176") (pin "1-VDD") (pinfunction "VDD_1-VDD") (pintype "power_in"))
      (node (ref "D177") (pin "1-VDD") (pinfunction "VDD_1-VDD") (pintype "power_in"))
      (node (ref "D178") (pin "1-VDD") (pinfunction "VDD_1-VDD") (pintype "power_in"))
      (node (ref "D179") (pin "1-VDD") (pinfunction "VDD_1-VDD") (pintype "power_in"))
      (node (ref "D180") (pin "1-VDD") (pinfunction "VDD_1-VDD") (pintype "power_in"))
      (node (ref "D181") (pin "1-VDD") (pinfunction "VDD_1-VDD") (pintype "power_in"))
      (node (ref "D182") (pin "1-VDD") (pinfunction "VDD_1-VDD") (pintype "power_in"))
      (node (ref "D183") (pin "1-VDD") (pinfunction "VDD_1-VDD") (pintype "power_in"))
      (node (ref "D184") (pin "1-VDD") (pinfunction "VDD_1-VDD") (pintype "power_in"))
      (node (ref "D185") (pin "1-VDD") (pinfunction "VDD_1-VDD") (pintype "power_in"))
      (node (ref "D186") (pin "1-VDD") (pinfunction "VDD_1-VDD") (pintype "power_in"))
      (node (ref "D187") (pin "1-VDD") (pinfunction "VDD_1-VDD") (pintype "power_in"))
      (node (ref "D188") (pin "1-VDD") (pinfunction "VDD_1-VDD") (pintype "power_in"))
      (node (ref "D189") (pin "1-VDD") (pinfunction "VDD_1-VDD") (pintype "power_in"))
      (node (ref "D190") (pin "1-VDD") (pinfunction "VDD_1-VDD") (pintype "power_in"))
      (node (ref "D191") (pin "1-VDD") (pinfunction "VDD_1-VDD") (pintype "power_in"))
      (node (ref "D192") (pin "1-VDD") (pinfunction "VDD_1-VDD") (pintype "power_in"))
    )
    (net (code "2") (name "/ROW_6_7") (class "Default")
      (node (ref "R9") (pin "2") (pinfunction "2_2") (pintype "passive"))
    )
    (net (code "3") (name "/ROW_8_9") (class "Default")
      (node (ref "D192") (pin "2-DOUT") (pinfunction "DO_2-DOUT") (pintype "output"))
    )
    (net (code "4") (name "/SIG4") (class "Default")
      (node (ref "R10") (pin "1") (pinfunction "1_1") (pintype "passive"))
    )
    (net (code "5") (name "GND") (class "Default")
      (node (ref "C145") (pin "1") (pinfunction "1_1") (pintype "passive"))
      (node (ref "C146") (pin "1") (pinfunction "1_1") (pintype "passive"))
      (node (ref "C147") (pin "1") (pinfunction "1_1") (pintype "passive"))
      (node (ref "C148") (pin "1") (pinfunction "1_1") (pintype "passive"))
      (node (ref "C149") (pin "1") (pinfunction "1_1") (pintype "passive"))
      (node (ref "C150") (pin "1") (pinfunction "1_1") (pintype "passive"))
      (node (ref "C151") (pin "1") (pinfunction "1_1") (pintype "passive"))
      (node (ref "C152") (pin "1") (pinfunction "1_1") (pintype "passive"))
      (node (ref "C153") (pin "1") (pinfunction "1_1") (pintype "passive"))
      (node (ref "C154") (pin "1") (pinfunction "1_1") (pintype "passive"))
      (node (ref "C155") (pin "1") (pinfunction "1_1") (pintype "passive"))
      (node (ref "C156") (pin "1") (pinfunction "1_1") (pintype "passive"))
      (node (ref "C157") (pin "1") (pinfunction "1_1") (pintype "passive"))
      (node (ref "C158") (pin "1") (pinfunction "1_1") (pintype "passive"))
      (node (ref "C159") (pin "1") (pinfunction "1_1") (pintype "passive"))
      (node (ref "C160") (pin "1") (pinfunction "1_1") (pintype "passive"))
      (node (ref "C161") (pin "1") (pinfunction "1_1") (pintype "passive"))
      (node (ref "C162") (pin "1") (pinfunction "1_1") (pintype "passive"))
      (node (ref "C163") (pin "1") (pinfunction "1_1") (pintype "passive"))
      (node (ref "C164") (pin "1") (pinfunction "1_1") (pintype "passive"))
      (node (ref "C165") (pin "1") (pinfunction "1_1") (pintype "passive"))
      (node (ref "C166") (pin "1") (pinfunction "1_1") (pintype "passive"))
      (node (ref "C167") (pin "1") (pinfunction "1_1") (pintype "passive"))
      (node (ref "C168") (pin "1") (pinfunction "1_1") (pintype "passive"))
      (node (ref "C169") (pin "1") (pinfunction "1_1") (pintype "passive"))
      (node (ref "C170") (pin "1") (pinfunction "1_1") (pintype "passive"))
      (node (ref "C171") (pin "1") (pinfunction "1_1") (pintype "passive"))
      (node (ref "C172") (pin "1") (pinfunction "1_1") (pintype "passive"))
      (node (ref "C173") (pin "1") (pinfunction "1_1") (pintype "passive"))
      (node (ref "C174") (pin "1") (pinfunction "1_1") (pintype "passive"))
      (node (ref "C175") (pin "1") (pinfunction "1_1") (pintype "passive"))
      (node (ref "C176") (pin "1") (pinfunction "1_1") (pintype "passive"))
      (node (ref "C177") (pin "1") (pinfunction "1_1") (pintype "passive"))
      (node (ref "C178") (pin "1") (pinfunction "1_1") (pintype "passive"))
      (node (ref "C179") (pin "1") (pinfunction "1_1") (pintype "passive"))
      (node (ref "C180") (pin "1") (pinfunction "1_1") (pintype "passive"))
      (node (ref "C181") (pin "1") (pinfunction "1_1") (pintype "passive"))
      (node (ref "C182") (pin "1") (pinfunction "1_1") (pintype "passive"))
      (node (ref "C183") (pin "1") (pinfunction "1_1") (pintype "passive"))
      (node (ref "C184") (pin "1") (pinfunction "1_1") (pintype "passive"))
      (node (ref "C185") (pin "1") (pinfunction "1_1") (pintype "passive"))
      (node (ref "C186") (pin "1") (pinfunction "1_1") (pintype "passive"))
      (node (ref "C187") (pin "1") (pinfunction "1_1") (pintype "passive"))
      (node (ref "C188") (pin "1") (pinfunction "1_1") (pintype "passive"))
      (node (ref "C189") (pin "1") (pinfunction "1_1") (pintype "passive"))
      (node (ref "C190") (pin "1") (pinfunction "1_1") (pintype "passive"))
      (node (ref "C191") (pin "1") (pinfunction "1_1") (pintype "passive"))
      (node (ref "C192") (pin "1") (pinfunction "1_1") (pintype "passive"))
      (node (ref "D145") (pin "3-GND") (pinfunction "GND_3-GND") (pintype "power_in"))
      (node (ref "D146") (pin "3-GND") (pinfunction "GND_3-GND") (pintype "power_in"))
      (node (ref "D147") (pin "3-GND") (pinfunction "GND_3-GND") (pintype "power_in"))
      (node (ref "D148") (pin "3-GND") (pinfunction "GND_3-GND") (pintype "power_in"))
      (node (ref "D149") (pin "3-GND") (pinfunction "GND_3-GND") (pintype "power_in"))
      (node (ref "D150") (pin "3-GND") (pinfunction "GND_3-GND") (pintype "power_in"))
      (node (ref "D151") (pin "3-GND") (pinfunction "GND_3-GND") (pintype "power_in"))
      (node (ref "D152") (pin "3-GND") (pinfunction "GND_3-GND") (pintype "power_in"))
      (node (ref "D153") (pin "3-GND") (pinfunction "GND_3-GND") (pintype "power_in"))
      (node (ref "D154") (pin "3-GND") (pinfunction "GND_3-GND") (pintype "power_in"))
      (node (ref "D155") (pin "3-GND") (pinfunction "GND_3-GND") (pintype "power_in"))
      (node (ref "D156") (pin "3-GND") (pinfunction "GND_3-GND") (pintype "power_in"))
      (node (ref "D157") (pin "3-GND") (pinfunction "GND_3-GND") (pintype "power_in"))
      (node (ref "D158") (pin "3-GND") (pinfunction "GND_3-GND") (pintype "power_in"))
      (node (ref "D159") (pin "3-GND") (pinfunction "GND_3-GND") (pintype "power_in"))
      (node (ref "D160") (pin "3-GND") (pinfunction "GND_3-GND") (pintype "power_in"))
      (node (ref "D161") (pin "3-GND") (pinfunction "GND_3-GND") (pintype "power_in"))
      (node (ref "D162") (pin "3-GND") (pinfunction "GND_3-GND") (pintype "power_in"))
      (node (ref "D163") (pin "3-GND") (pinfunction "GND_3-GND") (pintype "power_in"))
      (node (ref "D164") (pin "3-GND") (pinfunction "GND_3-GND") (pintype "power_in"))
      (node (ref "D165") (pin "3-GND") (pinfunction "GND_3-GND") (pintype "power_in"))
      (node (ref "D166") (pin "3-GND") (pinfunction "GND_3-GND") (pintype "power_in"))
      (node (ref "D167") (pin "3-GND") (pinfunction "GND_3-GND") (pintype "power_in"))
      (node (ref "D168") (pin "3-GND") (pinfunction "GND_3-GND") (pintype "power_in"))
      (node (ref "D169") (pin "3-GND") (pinfunction "GND_3-GND") (pintype "power_in"))
      (node (ref "D170") (pin "3-GND") (pinfunction "GND_3-GND") (pintype "power_in"))
      (node (ref "D171") (pin "3-GND") (pinfunction "GND_3-GND") (pintype "power_in"))
      (node (ref "D172") (pin "3-GND") (pinfunction "GND_3-GND") (pintype "power_in"))
      (node (ref "D173") (pin "3-GND") (pinfunction "GND_3-GND") (pintype "power_in"))
      (node (ref "D174") (pin "3-GND") (pinfunction "GND_3-GND") (pintype "power_in"))
      (node (ref "D175") (pin "3-GND") (pinfunction "GND_3-GND") (pintype "power_in"))
      (node (ref "D176") (pin "3-GND") (pinfunction "GND_3-GND") (pintype "power_in"))
      (node (ref "D177") (pin "3-GND") (pinfunction "GND_3-GND") (pintype "power_in"))
      (node (ref "D178") (pin "3-GND") (pinfunction "GND_3-GND") (pintype "power_in"))
      (node (ref "D179") (pin "3-GND") (pinfunction "GND_3-GND") (pintype "power_in"))
      (node (ref "D180") (pin "3-GND") (pinfunction "GND_3-GND") (pintype "power_in"))
      (node (ref "D181") (pin "3-GND") (pinfunction "GND_3-GND") (pintype "power_in"))
      (node (ref "D182") (pin "3-GND") (pinfunction "GND_3-GND") (pintype "power_in"))
      (node (ref "D183") (pin "3-GND") (pinfunction "GND_3-GND") (pintype "power_in"))
      (node (ref "D184") (pin "3-GND") (pinfunction "GND_3-GND") (pintype "power_in"))
      (node (ref "D185") (pin "3-GND") (pinfunction "GND_3-GND") (pintype "power_in"))
      (node (ref "D186") (pin "3-GND") (pinfunction "GND_3-GND") (pintype "power_in"))
      (node (ref "D187") (pin "3-GND") (pinfunction "GND_3-GND") (pintype "power_in"))
      (node (ref "D188") (pin "3-GND") (pinfunction "GND_3-GND") (pintype "power_in"))
      (node (ref "D189") (pin "3-GND") (pinfunction "GND_3-GND") (pintype "power_in"))
      (node (ref "D190") (pin "3-GND") (pinfunction "GND_3-GND") (pintype "power_in"))
      (node (ref "D191") (pin "3-GND") (pinfunction "GND_3-GND") (pintype "power_in"))
      (node (ref "D192") (pin "3-GND") (pinfunction "GND_3-GND") (pintype "power_in"))
    )
    (net (code "6") (name "Net-(D145-DI)") (class "Default")
      (node (ref "D145") (pin "4-DIN") (pinfunction "DI_4-DIN") (pintype "input"))
      (node (ref "R10") (pin "2") (pinfunction "2_2") (pintype "passive"))
      (node (ref "R9") (pin "1") (pinfunction "1_1") (pintype "passive"))
    )
    (net (code "7") (name "Net-(D145-DO)") (class "Default")
      (node (ref "D145") (pin "2-DOUT") (pinfunction "DO_2-DOUT") (pintype "output"))
      (node (ref "D146") (pin "4-DIN") (pinfunction "DI_4-DIN") (pintype "input"))
    )
    (net (code "8") (name "Net-(D146-DO)") (class "Default")
      (node (ref "D146") (pin "2-DOUT") (pinfunction "DO_2-DOUT") (pintype "output"))
      (node (ref "D147") (pin "4-DIN") (pinfunction "DI_4-DIN") (pintype "input"))
    )
    (net (code "9") (name "Net-(D147-DO)") (class "Default")
      (node (ref "D147") (pin "2-DOUT") (pinfunction "DO_2-DOUT") (pintype "output"))
      (node (ref "D148") (pin "4-DIN") (pinfunction "DI_4-DIN") (pintype "input"))
    )
    (net (code "10") (name "Net-(D148-DO)") (class "Default")
      (node (ref "D148") (pin "2-DOUT") (pinfunction "DO_2-DOUT") (pintype "output"))
      (node (ref "D149") (pin "4-DIN") (pinfunction "DI_4-DIN") (pintype "input"))
    )
    (net (code "11") (name "Net-(D149-DO)") (class "Default")
      (node (ref "D149") (pin "2-DOUT") (pinfunction "DO_2-DOUT") (pintype "output"))
      (node (ref "D150") (pin "4-DIN") (pinfunction "DI_4-DIN") (pintype "input"))
    )
    (net (code "12") (name "Net-(D150-DO)") (class "Default")
      (node (ref "D150") (pin "2-DOUT") (pinfunction "DO_2-DOUT") (pintype "output"))
      (node (ref "D151") (pin "4-DIN") (pinfunction "DI_4-DIN") (pintype "input"))
    )
    (net (code "13") (name "Net-(D151-DO)") (class "Default")
      (node (ref "D151") (pin "2-DOUT") (pinfunction "DO_2-DOUT") (pintype "output"))
      (node (ref "D152") (pin "4-DIN") (pinfunction "DI_4-DIN") (pintype "input"))
    )
    (net (code "14") (name "Net-(D152-DO)") (class "Default")
      (node (ref "D152") (pin "2-DOUT") (pinfunction "DO_2-DOUT") (pintype "output"))
      (node (ref "D153") (pin "4-DIN") (pinfunction "DI_4-DIN") (pintype "input"))
    )
    (net (code "15") (name "Net-(D153-DO)") (class "Default")
      (node (ref "D153") (pin "2-DOUT") (pinfunction "DO_2-DOUT") (pintype "output"))
      (node (ref "D154") (pin "4-DIN") (pinfunction "DI_4-DIN") (pintype "input"))
    )
    (net (code "16") (name "Net-(D154-DO)") (class "Default")
      (node (ref "D154") (pin "2-DOUT") (pinfunction "DO_2-DOUT") (pintype "output"))
      (node (ref "D155") (pin "4-DIN") (pinfunction "DI_4-DIN") (pintype "input"))
    )
    (net (code "17") (name "Net-(D155-DO)") (class "Default")
      (node (ref "D155") (pin "2-DOUT") (pinfunction "DO_2-DOUT") (pintype "output"))
      (node (ref "D156") (pin "4-DIN") (pinfunction "DI_4-DIN") (pintype "input"))
    )
    (net (code "18") (name "Net-(D156-DO)") (class "Default")
      (node (ref "D156") (pin "2-DOUT") (pinfunction "DO_2-DOUT") (pintype "output"))
      (node (ref "D157") (pin "4-DIN") (pinfunction "DI_4-DIN") (pintype "input"))
    )
    (net (code "19") (name "Net-(D157-DO)") (class "Default")
      (node (ref "D157") (pin "2-DOUT") (pinfunction "DO_2-DOUT") (pintype "output"))
      (node (ref "D158") (pin "4-DIN") (pinfunction "DI_4-DIN") (pintype "input"))
    )
    (net (code "20") (name "Net-(D158-DO)") (class "Default")
      (node (ref "D158") (pin "2-DOUT") (pinfunction "DO_2-DOUT") (pintype "output"))
      (node (ref "D159") (pin "4-DIN") (pinfunction "DI_4-DIN") (pintype "input"))
    )
    (net (code "21") (name "Net-(D159-DO)") (class "Default")
      (node (ref "D159") (pin "2-DOUT") (pinfunction "DO_2-DOUT") (pintype "output"))
      (node (ref "D160") (pin "4-DIN") (pinfunction "DI_4-DIN") (pintype "input"))
    )
    (net (code "22") (name "Net-(D160-DO)") (class "Default")
      (node (ref "D160") (pin "2-DOUT") (pinfunction "DO_2-DOUT") (pintype "output"))
      (node (ref "D161") (pin "4-DIN") (pinfunction "DI_4-DIN") (pintype "input"))
    )
    (net (code "23") (name "Net-(D161-DO)") (class "Default")
      (node (ref "D161") (pin "2-DOUT") (pinfunction "DO_2-DOUT") (pintype "output"))
      (node (ref "D162") (pin "4-DIN") (pinfunction "DI_4-DIN") (pintype "input"))
    )
    (net (code "24") (name "Net-(D162-DO)") (class "Default")
      (node (ref "D162") (pin "2-DOUT") (pinfunction "DO_2-DOUT") (pintype "output"))
      (node (ref "D163") (pin "4-DIN") (pinfunction "DI_4-DIN") (pintype "input"))
    )
    (net (code "25") (name "Net-(D163-DO)") (class "Default")
      (node (ref "D163") (pin "2-DOUT") (pinfunction "DO_2-DOUT") (pintype "output"))
      (node (ref "D164") (pin "4-DIN") (pinfunction "DI_4-DIN") (pintype "input"))
    )
    (net (code "26") (name "Net-(D164-DO)") (class "Default")
      (node (ref "D164") (pin "2-DOUT") (pinfunction "DO_2-DOUT") (pintype "output"))
      (node (ref "D165") (pin "4-DIN") (pinfunction "DI_4-DIN") (pintype "input"))
    )
    (net (code "27") (name "Net-(D165-DO)") (class "Default")
      (node (ref "D165") (pin "2-DOUT") (pinfunction "DO_2-DOUT") (pintype "output"))
      (node (ref "D166") (pin "4-DIN") (pinfunction "DI_4-DIN") (pintype "input"))
    )
    (net (code "28") (name "Net-(D166-DO)") (class "Default")
      (node (ref "D166") (pin "2-DOUT") (pinfunction "DO_2-DOUT") (pintype "output"))
      (node (ref "D167") (pin "4-DIN") (pinfunction "DI_4-DIN") (pintype "input"))
    )
    (net (code "29") (name "Net-(D167-DO)") (class "Default")
      (node (ref "D167") (pin "2-DOUT") (pinfunction "DO_2-DOUT") (pintype "output"))
      (node (ref "D168") (pin "4-DIN") (pinfunction "DI_4-DIN") (pintype "input"))
    )
    (net (code "30") (name "Net-(D168-DO)") (class "Default")
      (node (ref "D168") (pin "2-DOUT") (pinfunction "DO_2-DOUT") (pintype "output"))
      (node (ref "R11") (pin "2") (pinfunction "2_2") (pintype "passive"))
    )
    (net (code "31") (name "Net-(D169-DI)") (class "Default")
      (node (ref "D169") (pin "4-DIN") (pinfunction "DI_4-DIN") (pintype "input"))
      (node (ref "R11") (pin "1") (pinfunction "1_1") (pintype "passive"))
    )
    (net (code "32") (name "Net-(D169-DO)") (class "Default")
      (node (ref "D169") (pin "2-DOUT") (pinfunction "DO_2-DOUT") (pintype "output"))
      (node (ref "D170") (pin "4-DIN") (pinfunction "DI_4-DIN") (pintype "input"))
    )
    (net (code "33") (name "Net-(D170-DO)") (class "Default")
      (node (ref "D170") (pin "2-DOUT") (pinfunction "DO_2-DOUT") (pintype "output"))
      (node (ref "D171") (pin "4-DIN") (pinfunction "DI_4-DIN") (pintype "input"))
    )
    (net (code "34") (name "Net-(D171-DO)") (class "Default")
      (node (ref "D171") (pin "2-DOUT") (pinfunction "DO_2-DOUT") (pintype "output"))
      (node (ref "D172") (pin "4-DIN") (pinfunction "DI_4-DIN") (pintype "input"))
    )
    (net (code "35") (name "Net-(D172-DO)") (class "Default")
      (node (ref "D172") (pin "2-DOUT") (pinfunction "DO_2-DOUT") (pintype "output"))
      (node (ref "D173") (pin "4-DIN") (pinfunction "DI_4-DIN") (pintype "input"))
    )
    (net (code "36") (name "Net-(D173-DO)") (class "Default")
      (node (ref "D173") (pin "2-DOUT") (pinfunction "DO_2-DOUT") (pintype "output"))
      (node (ref "D174") (pin "4-DIN") (pinfunction "DI_4-DIN") (pintype "input"))
    )
    (net (code "37") (name "Net-(D174-DO)") (class "Default")
      (node (ref "D174") (pin "2-DOUT") (pinfunction "DO_2-DOUT") (pintype "output"))
      (node (ref "D175") (pin "4-DIN") (pinfunction "DI_4-DIN") (pintype "input"))
    )
    (net (code "38") (name "Net-(D175-DO)") (class "Default")
      (node (ref "D175") (pin "2-DOUT") (pinfunction "DO_2-DOUT") (pintype "output"))
      (node (ref "D176") (pin "4-DIN") (pinfunction "DI_4-DIN") (pintype "input"))
    )
    (net (code "39") (name "Net-(D176-DO)") (class "Default")
      (node (ref "D176") (pin "2-DOUT") (pinfunction "DO_2-DOUT") (pintype "output"))
      (node (ref "D177") (pin "4-DIN") (pinfunction "DI_4-DIN") (pintype "input"))
    )
    (net (code "40") (name "Net-(D177-DO)") (class "Default")
      (node (ref "D177") (pin "2-DOUT") (pinfunction "DO_2-DOUT") (pintype "output"))
      (node (ref "D178") (pin "4-DIN") (pinfunction "DI_4-DIN") (pintype "input"))
    )
    (net (code "41") (name "Net-(D178-DO)") (class "Default")
      (node (ref "D178") (pin "2-DOUT") (pinfunction "DO_2-DOUT") (pintype "output"))
      (node (ref "D179") (pin "4-DIN") (pinfunction "DI_4-DIN") (pintype "input"))
    )
    (net (code "42") (name "Net-(D179-DO)") (class "Default")
      (node (ref "D179") (pin "2-DOUT") (pinfunction "DO_2-DOUT") (pintype "output"))
      (node (ref "D180") (pin "4-DIN") (pinfunction "DI_4-DIN") (pintype "input"))
    )
    (net (code "43") (name "Net-(D180-DO)") (class "Default")
      (node (ref "D180") (pin "2-DOUT") (pinfunction "DO_2-DOUT") (pintype "output"))
      (node (ref "D181") (pin "4-DIN") (pinfunction "DI_4-DIN") (pintype "input"))
    )
    (net (code "44") (name "Net-(D181-DO)") (class "Default")
      (node (ref "D181") (pin "2-DOUT") (pinfunction "DO_2-DOUT") (pintype "output"))
      (node (ref "D182") (pin "4-DIN") (pinfunction "DI_4-DIN") (pintype "input"))
    )
    (net (code "45") (name "Net-(D182-DO)") (class "Default")
      (node (ref "D182") (pin "2-DOUT") (pinfunction "DO_2-DOUT") (pintype "output"))
      (node (ref "D183") (pin "4-DIN") (pinfunction "DI_4-DIN") (pintype "input"))
    )
    (net (code "46") (name "Net-(D183-DO)") (class "Default")
      (node (ref "D183") (pin "2-DOUT") (pinfunction "DO_2-DOUT") (pintype "output"))
      (node (ref "D184") (pin "4-DIN") (pinfunction "DI_4-DIN") (pintype "input"))
    )
    (net (code "47") (name "Net-(D184-DO)") (class "Default")
      (node (ref "D184") (pin "2-DOUT") (pinfunction "DO_2-DOUT") (pintype "output"))
      (node (ref "D185") (pin "4-DIN") (pinfunction "DI_4-DIN") (pintype "input"))
    )
    (net (code "48") (name "Net-(D185-DO)") (class "Default")
      (node (ref "D185") (pin "2-DOUT") (pinfunction "DO_2-DOUT") (pintype "output"))
      (node (ref "D186") (pin "4-DIN") (pinfunction "DI_4-DIN") (pintype "input"))
    )
    (net (code "49") (name "Net-(D186-DO)") (class "Default")
      (node (ref "D186") (pin "2-DOUT") (pinfunction "DO_2-DOUT") (pintype "output"))
      (node (ref "D187") (pin "4-DIN") (pinfunction "DI_4-DIN") (pintype "input"))
    )
    (net (code "50") (name "Net-(D187-DO)") (class "Default")
      (node (ref "D187") (pin "2-DOUT") (pinfunction "DO_2-DOUT") (pintype "output"))
      (node (ref "D188") (pin "4-DIN") (pinfunction "DI_4-DIN") (pintype "input"))
    )
    (net (code "51") (name "Net-(D188-DO)") (class "Default")
      (node (ref "D188") (pin "2-DOUT") (pinfunction "DO_2-DOUT") (pintype "output"))
      (node (ref "D189") (pin "4-DIN") (pinfunction "DI_4-DIN") (pintype "input"))
    )
    (net (code "52") (name "Net-(D189-DO)") (class "Default")
      (node (ref "D189") (pin "2-DOUT") (pinfunction "DO_2-DOUT") (pintype "output"))
      (node (ref "D190") (pin "4-DIN") (pinfunction "DI_4-DIN") (pintype "input"))
    )
    (net (code "53") (name "Net-(D190-DO)") (class "Default")
      (node (ref "D190") (pin "2-DOUT") (pinfunction "DO_2-DOUT") (pintype "output"))
      (node (ref "D191") (pin "4-DIN") (pinfunction "DI_4-DIN") (pintype "input"))
    )
    (net (code "54") (name "Net-(D191-DO)") (class "Default")
      (node (ref "D191") (pin "2-DOUT") (pinfunction "DO_2-DOUT") (pintype "output"))
      (node (ref "D192") (pin "4-DIN") (pinfunction "DI_4-DIN") (pintype "input"))
    )
  )
)
